# PowerSupplies.net
KiCad netlist of a schematic drawn in Altium Designer
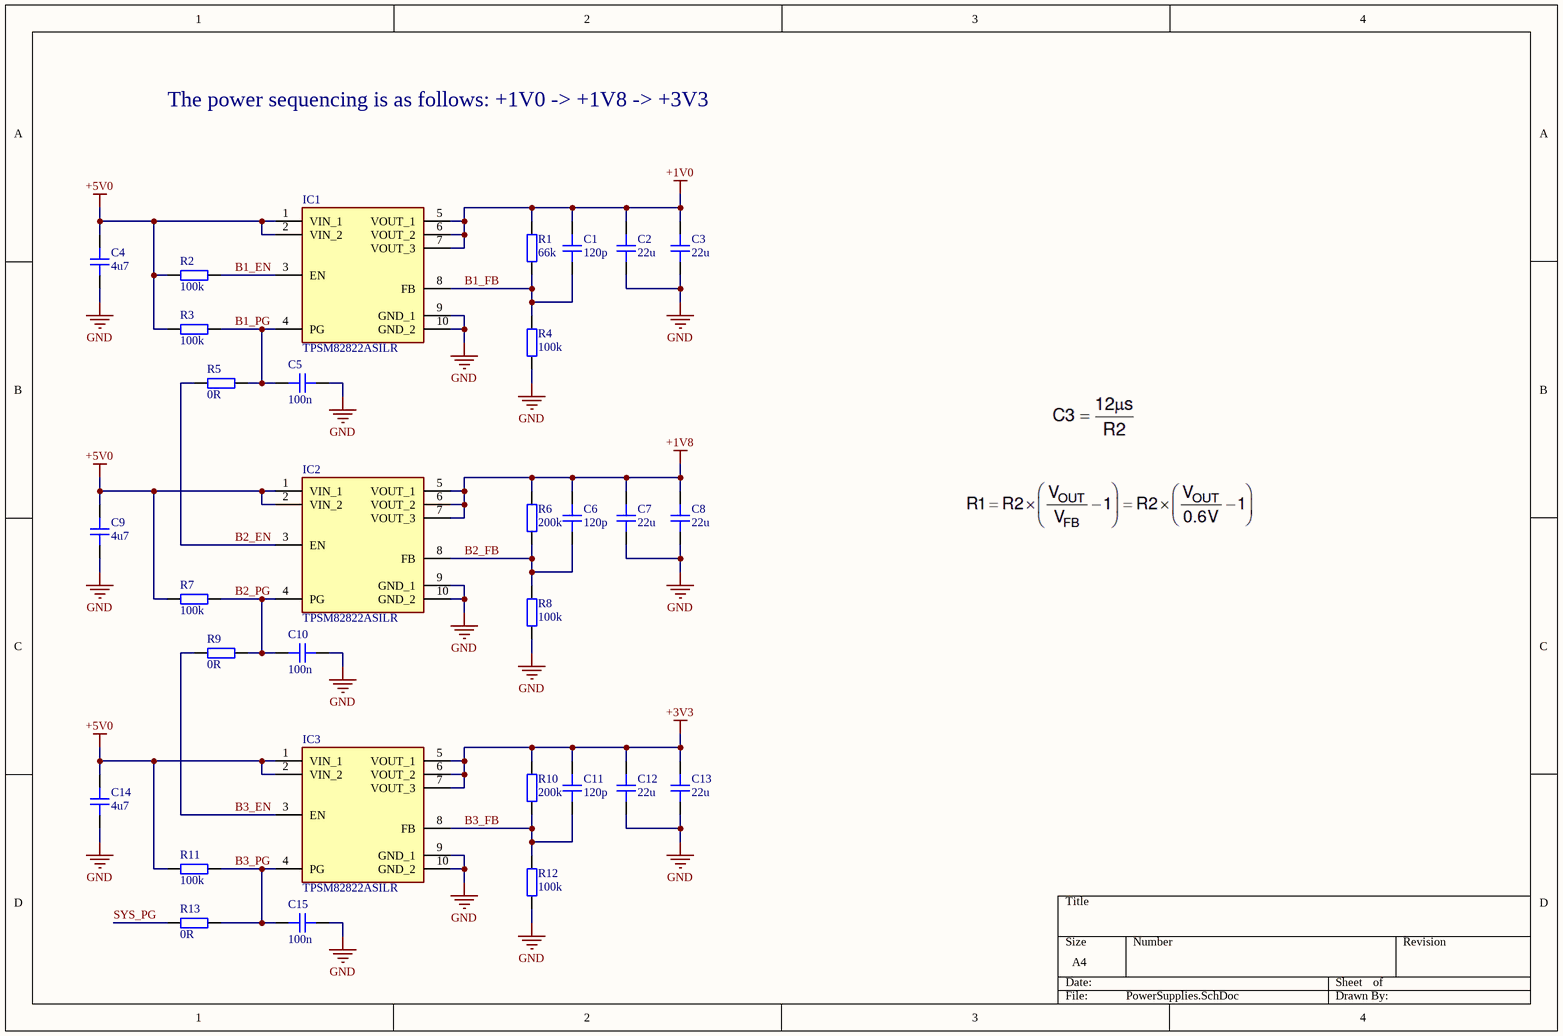
[diagram p0: PowerSupplies.SchDoc]

(export (version "E")
  (design (tool "Eeschema 10.0.6"))
  (components
    (comp (ref "C1")
      (value "120p")
      (footprint "CAP_0402")
      (description "Capacitor SMD 0402")
      (libsource (lib "Schematic-Lib-PhilsLab") (part "CAP_0402"))
    )
    (comp (ref "C2")
      (value "22u")
      (footprint "CAP_0603")
      (description "Capacitor SMD 0603")
      (libsource (lib "Schematic-Lib-PhilsLab") (part "CAP_0603"))
    )
    (comp (ref "C3")
      (value "22u")
      (footprint "CAP_0603")
      (description "Capacitor SMD 0603")
      (libsource (lib "Schematic-Lib-PhilsLab") (part "CAP_0603"))
    )
    (comp (ref "C4")
      (value "4u7")
      (footprint "CAP_0402")
      (description "Capacitor SMD 0402")
      (libsource (lib "Schematic-Lib-PhilsLab") (part "CAP_0402"))
    )
    (comp (ref "C5")
      (value "100n")
      (footprint "CAP_0402")
      (description "Capacitor SMD 0402")
      (libsource (lib "Schematic-Lib-PhilsLab") (part "CAP_0402"))
    )
    (comp (ref "C6")
      (value "120p")
      (footprint "CAP_0402")
      (description "Capacitor SMD 0402")
      (libsource (lib "Schematic-Lib-PhilsLab") (part "CAP_0402"))
    )
    (comp (ref "C7")
      (value "22u")
      (footprint "CAP_0603")
      (description "Capacitor SMD 0603")
      (libsource (lib "Schematic-Lib-PhilsLab") (part "CAP_0603"))
    )
    (comp (ref "C8")
      (value "22u")
      (footprint "CAP_0603")
      (description "Capacitor SMD 0603")
      (libsource (lib "Schematic-Lib-PhilsLab") (part "CAP_0603"))
    )
    (comp (ref "C9")
      (value "4u7")
      (footprint "CAP_0402")
      (description "Capacitor SMD 0402")
      (libsource (lib "Schematic-Lib-PhilsLab") (part "CAP_0402"))
    )
    (comp (ref "C10")
      (value "100n")
      (footprint "CAP_0402")
      (description "Capacitor SMD 0402")
      (libsource (lib "Schematic-Lib-PhilsLab") (part "CAP_0402"))
    )
    (comp (ref "C11")
      (value "120p")
      (footprint "CAP_0402")
      (description "Capacitor SMD 0402")
      (libsource (lib "Schematic-Lib-PhilsLab") (part "CAP_0402"))
    )
    (comp (ref "C12")
      (value "22u")
      (footprint "CAP_0603")
      (description "Capacitor SMD 0603")
      (libsource (lib "Schematic-Lib-PhilsLab") (part "CAP_0603"))
    )
    (comp (ref "C13")
      (value "22u")
      (footprint "CAP_0603")
      (description "Capacitor SMD 0603")
      (libsource (lib "Schematic-Lib-PhilsLab") (part "CAP_0603"))
    )
    (comp (ref "C14")
      (value "4u7")
      (footprint "CAP_0402")
      (description "Capacitor SMD 0402")
      (libsource (lib "Schematic-Lib-PhilsLab") (part "CAP_0402"))
    )
    (comp (ref "C15")
      (value "100n")
      (footprint "CAP_0402")
      (description "Capacitor SMD 0402")
      (libsource (lib "Schematic-Lib-PhilsLab") (part "CAP_0402"))
    )
    (comp (ref "IC1")
      (value "TPSM82822ASILR")
      (footprint "Footprint-Lib-PhilsLab:TPSM82822ASILR")
      (description "Integrated Circuit")
      (fields (field (name "MOUSER PART NUMBER") "595-TPSM82822ASILR"))
      (libsource (lib "Schematic-Lib-PhilsLab") (part "TPSM82822ASILR"))
    )
    (comp (ref "IC2")
      (value "TPSM82822ASILR")
      (footprint "Footprint-Lib-PhilsLab:TPSM82822ASILR")
      (description "Integrated Circuit")
      (fields (field (name "MOUSER PART NUMBER") "595-TPSM82822ASILR"))
      (libsource (lib "Schematic-Lib-PhilsLab") (part "TPSM82822ASILR"))
    )
    (comp (ref "IC3")
      (value "TPSM82822ASILR")
      (footprint "Footprint-Lib-PhilsLab:TPSM82822ASILR")
      (description "Integrated Circuit")
      (fields (field (name "MOUSER PART NUMBER") "595-TPSM82822ASILR"))
      (libsource (lib "Schematic-Lib-PhilsLab") (part "TPSM82822ASILR"))
    )
    (comp (ref "R1")
      (value "66k")
      (footprint "RES_0402")
      (description "Resistor SMD 0402")
      (libsource (lib "Schematic-Lib-PhilsLab") (part "RES_0402"))
    )
    (comp (ref "R2")
      (value "100k")
      (footprint "RES_0402")
      (description "Resistor SMD 0402")
      (libsource (lib "Schematic-Lib-PhilsLab") (part "RES_0402"))
    )
    (comp (ref "R3")
      (value "100k")
      (footprint "RES_0402")
      (description "Resistor SMD 0402")
      (libsource (lib "Schematic-Lib-PhilsLab") (part "RES_0402"))
    )
    (comp (ref "R4")
      (value "100k")
      (footprint "RES_0402")
      (description "Resistor SMD 0402")
      (libsource (lib "Schematic-Lib-PhilsLab") (part "RES_0402"))
    )
    (comp (ref "R5")
      (value "0R")
      (footprint "RES_0402")
      (description "Resistor SMD 0402")
      (libsource (lib "Schematic-Lib-PhilsLab") (part "RES_0402"))
    )
    (comp (ref "R6")
      (value "200k")
      (footprint "RES_0402")
      (description "Resistor SMD 0402")
      (libsource (lib "Schematic-Lib-PhilsLab") (part "RES_0402"))
    )
    (comp (ref "R7")
      (value "100k")
      (footprint "RES_0402")
      (description "Resistor SMD 0402")
      (libsource (lib "Schematic-Lib-PhilsLab") (part "RES_0402"))
    )
    (comp (ref "R8")
      (value "100k")
      (footprint "RES_0402")
      (description "Resistor SMD 0402")
      (libsource (lib "Schematic-Lib-PhilsLab") (part "RES_0402"))
    )
    (comp (ref "R9")
      (value "0R")
      (footprint "RES_0402")
      (description "Resistor SMD 0402")
      (libsource (lib "Schematic-Lib-PhilsLab") (part "RES_0402"))
    )
    (comp (ref "R10")
      (value "200k")
      (footprint "RES_0402")
      (description "Resistor SMD 0402")
      (libsource (lib "Schematic-Lib-PhilsLab") (part "RES_0402"))
    )
    (comp (ref "R11")
      (value "100k")
      (footprint "RES_0402")
      (description "Resistor SMD 0402")
      (libsource (lib "Schematic-Lib-PhilsLab") (part "RES_0402"))
    )
    (comp (ref "R12")
      (value "100k")
      (footprint "RES_0402")
      (description "Resistor SMD 0402")
      (libsource (lib "Schematic-Lib-PhilsLab") (part "RES_0402"))
    )
    (comp (ref "R13")
      (value "0R")
      (footprint "RES_0402")
      (description "Resistor SMD 0402")
      (libsource (lib "Schematic-Lib-PhilsLab") (part "RES_0402"))
    )
  )
  (nets
    (net (code "1") (name "+1V0") (class "Default")
      (node (ref "C1") (pin "2") (pinfunction "2_2") (pintype "passive"))
      (node (ref "C2") (pin "2") (pinfunction "2_2") (pintype "passive"))
      (node (ref "C3") (pin "2") (pinfunction "2_2") (pintype "passive"))
      (node (ref "IC1") (pin "5") (pinfunction "VOUT_1_5") (pintype "passive"))
      (node (ref "IC1") (pin "6") (pinfunction "VOUT_2_6") (pintype "passive"))
      (node (ref "IC1") (pin "7") (pinfunction "VOUT_3_7") (pintype "passive"))
      (node (ref "R1") (pin "2") (pinfunction "2_2") (pintype "passive"))
    )
    (net (code "2") (name "+1V8") (class "Default")
      (node (ref "C6") (pin "2") (pinfunction "2_2") (pintype "passive"))
      (node (ref "C7") (pin "2") (pinfunction "2_2") (pintype "passive"))
      (node (ref "C8") (pin "2") (pinfunction "2_2") (pintype "passive"))
      (node (ref "IC2") (pin "5") (pinfunction "VOUT_1_5") (pintype "passive"))
      (node (ref "IC2") (pin "6") (pinfunction "VOUT_2_6") (pintype "passive"))
      (node (ref "IC2") (pin "7") (pinfunction "VOUT_3_7") (pintype "passive"))
      (node (ref "R6") (pin "2") (pinfunction "2_2") (pintype "passive"))
    )
    (net (code "3") (name "+3V3") (class "Default")
      (node (ref "C11") (pin "2") (pinfunction "2_2") (pintype "passive"))
      (node (ref "C12") (pin "2") (pinfunction "2_2") (pintype "passive"))
      (node (ref "C13") (pin "2") (pinfunction "2_2") (pintype "passive"))
      (node (ref "IC3") (pin "5") (pinfunction "VOUT_1_5") (pintype "passive"))
      (node (ref "IC3") (pin "6") (pinfunction "VOUT_2_6") (pintype "passive"))
      (node (ref "IC3") (pin "7") (pinfunction "VOUT_3_7") (pintype "passive"))
      (node (ref "R10") (pin "2") (pinfunction "2_2") (pintype "passive"))
    )
    (net (code "4") (name "+5V0") (class "Default")
      (node (ref "C14") (pin "2") (pinfunction "2_2") (pintype "passive"))
      (node (ref "C4") (pin "2") (pinfunction "2_2") (pintype "passive"))
      (node (ref "C9") (pin "2") (pinfunction "2_2") (pintype "passive"))
      (node (ref "IC1") (pin "1") (pinfunction "VIN_1_1") (pintype "passive"))
      (node (ref "IC1") (pin "2") (pinfunction "VIN_2_2") (pintype "passive"))
      (node (ref "IC2") (pin "1") (pinfunction "VIN_1_1") (pintype "passive"))
      (node (ref "IC2") (pin "2") (pinfunction "VIN_2_2") (pintype "passive"))
      (node (ref "IC3") (pin "1") (pinfunction "VIN_1_1") (pintype "passive"))
      (node (ref "IC3") (pin "2") (pinfunction "VIN_2_2") (pintype "passive"))
      (node (ref "R11") (pin "1") (pinfunction "1_1") (pintype "passive"))
      (node (ref "R2") (pin "1") (pinfunction "1_1") (pintype "passive"))
      (node (ref "R3") (pin "1") (pinfunction "1_1") (pintype "passive"))
      (node (ref "R7") (pin "1") (pinfunction "1_1") (pintype "passive"))
    )
    (net (code "5") (name "/B1_EN") (class "Default")
      (node (ref "IC1") (pin "3") (pinfunction "EN_3") (pintype "passive"))
      (node (ref "R2") (pin "2") (pinfunction "2_2") (pintype "passive"))
    )
    (net (code "6") (name "/B1_FB") (class "Default")
      (node (ref "C1") (pin "1") (pinfunction "1_1") (pintype "passive"))
      (node (ref "IC1") (pin "8") (pinfunction "FB_8") (pintype "passive"))
      (node (ref "R1") (pin "1") (pinfunction "1_1") (pintype "passive"))
      (node (ref "R4") (pin "2") (pinfunction "2_2") (pintype "passive"))
    )
    (net (code "7") (name "/B1_PG") (class "Default")
      (node (ref "C5") (pin "2") (pinfunction "2_2") (pintype "passive"))
      (node (ref "IC1") (pin "4") (pinfunction "PG_4") (pintype "passive"))
      (node (ref "R3") (pin "2") (pinfunction "2_2") (pintype "passive"))
      (node (ref "R5") (pin "2") (pinfunction "2_2") (pintype "passive"))
    )
    (net (code "8") (name "/B2_EN") (class "Default")
      (node (ref "IC2") (pin "3") (pinfunction "EN_3") (pintype "passive"))
      (node (ref "R5") (pin "1") (pinfunction "1_1") (pintype "passive"))
    )
    (net (code "9") (name "/B2_FB") (class "Default")
      (node (ref "C6") (pin "1") (pinfunction "1_1") (pintype "passive"))
      (node (ref "IC2") (pin "8") (pinfunction "FB_8") (pintype "passive"))
      (node (ref "R6") (pin "1") (pinfunction "1_1") (pintype "passive"))
      (node (ref "R8") (pin "2") (pinfunction "2_2") (pintype "passive"))
    )
    (net (code "10") (name "/B2_PG") (class "Default")
      (node (ref "C10") (pin "2") (pinfunction "2_2") (pintype "passive"))
      (node (ref "IC2") (pin "4") (pinfunction "PG_4") (pintype "passive"))
      (node (ref "R7") (pin "2") (pinfunction "2_2") (pintype "passive"))
      (node (ref "R9") (pin "2") (pinfunction "2_2") (pintype "passive"))
    )
    (net (code "11") (name "/B3_EN") (class "Default")
      (node (ref "IC3") (pin "3") (pinfunction "EN_3") (pintype "passive"))
      (node (ref "R9") (pin "1") (pinfunction "1_1") (pintype "passive"))
    )
    (net (code "12") (name "/B3_FB") (class "Default")
      (node (ref "C11") (pin "1") (pinfunction "1_1") (pintype "passive"))
      (node (ref "IC3") (pin "8") (pinfunction "FB_8") (pintype "passive"))
      (node (ref "R10") (pin "1") (pinfunction "1_1") (pintype "passive"))
      (node (ref "R12") (pin "2") (pinfunction "2_2") (pintype "passive"))
    )
    (net (code "13") (name "/B3_PG") (class "Default")
      (node (ref "C15") (pin "2") (pinfunction "2_2") (pintype "passive"))
      (node (ref "IC3") (pin "4") (pinfunction "PG_4") (pintype "passive"))
      (node (ref "R11") (pin "2") (pinfunction "2_2") (pintype "passive"))
      (node (ref "R13") (pin "2") (pinfunction "2_2") (pintype "passive"))
    )
    (net (code "14") (name "/SYS_PG") (class "Default")
      (node (ref "R13") (pin "1") (pinfunction "1_1") (pintype "passive"))
    )
    (net (code "15") (name "GND") (class "Default")
      (node (ref "C10") (pin "1") (pinfunction "1_1") (pintype "passive"))
      (node (ref "C12") (pin "1") (pinfunction "1_1") (pintype "passive"))
      (node (ref "C13") (pin "1") (pinfunction "1_1") (pintype "passive"))
      (node (ref "C14") (pin "1") (pinfunction "1_1") (pintype "passive"))
      (node (ref "C15") (pin "1") (pinfunction "1_1") (pintype "passive"))
      (node (ref "C2") (pin "1") (pinfunction "1_1") (pintype "passive"))
      (node (ref "C3") (pin "1") (pinfunction "1_1") (pintype "passive"))
      (node (ref "C4") (pin "1") (pinfunction "1_1") (pintype "passive"))
      (node (ref "C5") (pin "1") (pinfunction "1_1") (pintype "passive"))
      (node (ref "C7") (pin "1") (pinfunction "1_1") (pintype "passive"))
      (node (ref "C8") (pin "1") (pinfunction "1_1") (pintype "passive"))
      (node (ref "C9") (pin "1") (pinfunction "1_1") (pintype "passive"))
      (node (ref "IC1") (pin "10") (pinfunction "GND_2_10") (pintype "passive"))
      (node (ref "IC1") (pin "9") (pinfunction "GND_1_9") (pintype "passive"))
      (node (ref "IC2") (pin "10") (pinfunction "GND_2_10") (pintype "passive"))
      (node (ref "IC2") (pin "9") (pinfunction "GND_1_9") (pintype "passive"))
      (node (ref "IC3") (pin "10") (pinfunction "GND_2_10") (pintype "passive"))
      (node (ref "IC3") (pin "9") (pinfunction "GND_1_9") (pintype "passive"))
      (node (ref "R12") (pin "1") (pinfunction "1_1") (pintype "passive"))
      (node (ref "R4") (pin "1") (pinfunction "1_1") (pintype "passive"))
      (node (ref "R8") (pin "1") (pinfunction "1_1") (pintype "passive"))
    )
  )
)
